# pa_only_900.net
KiCad netlist of a schematic drawn in EAGLE
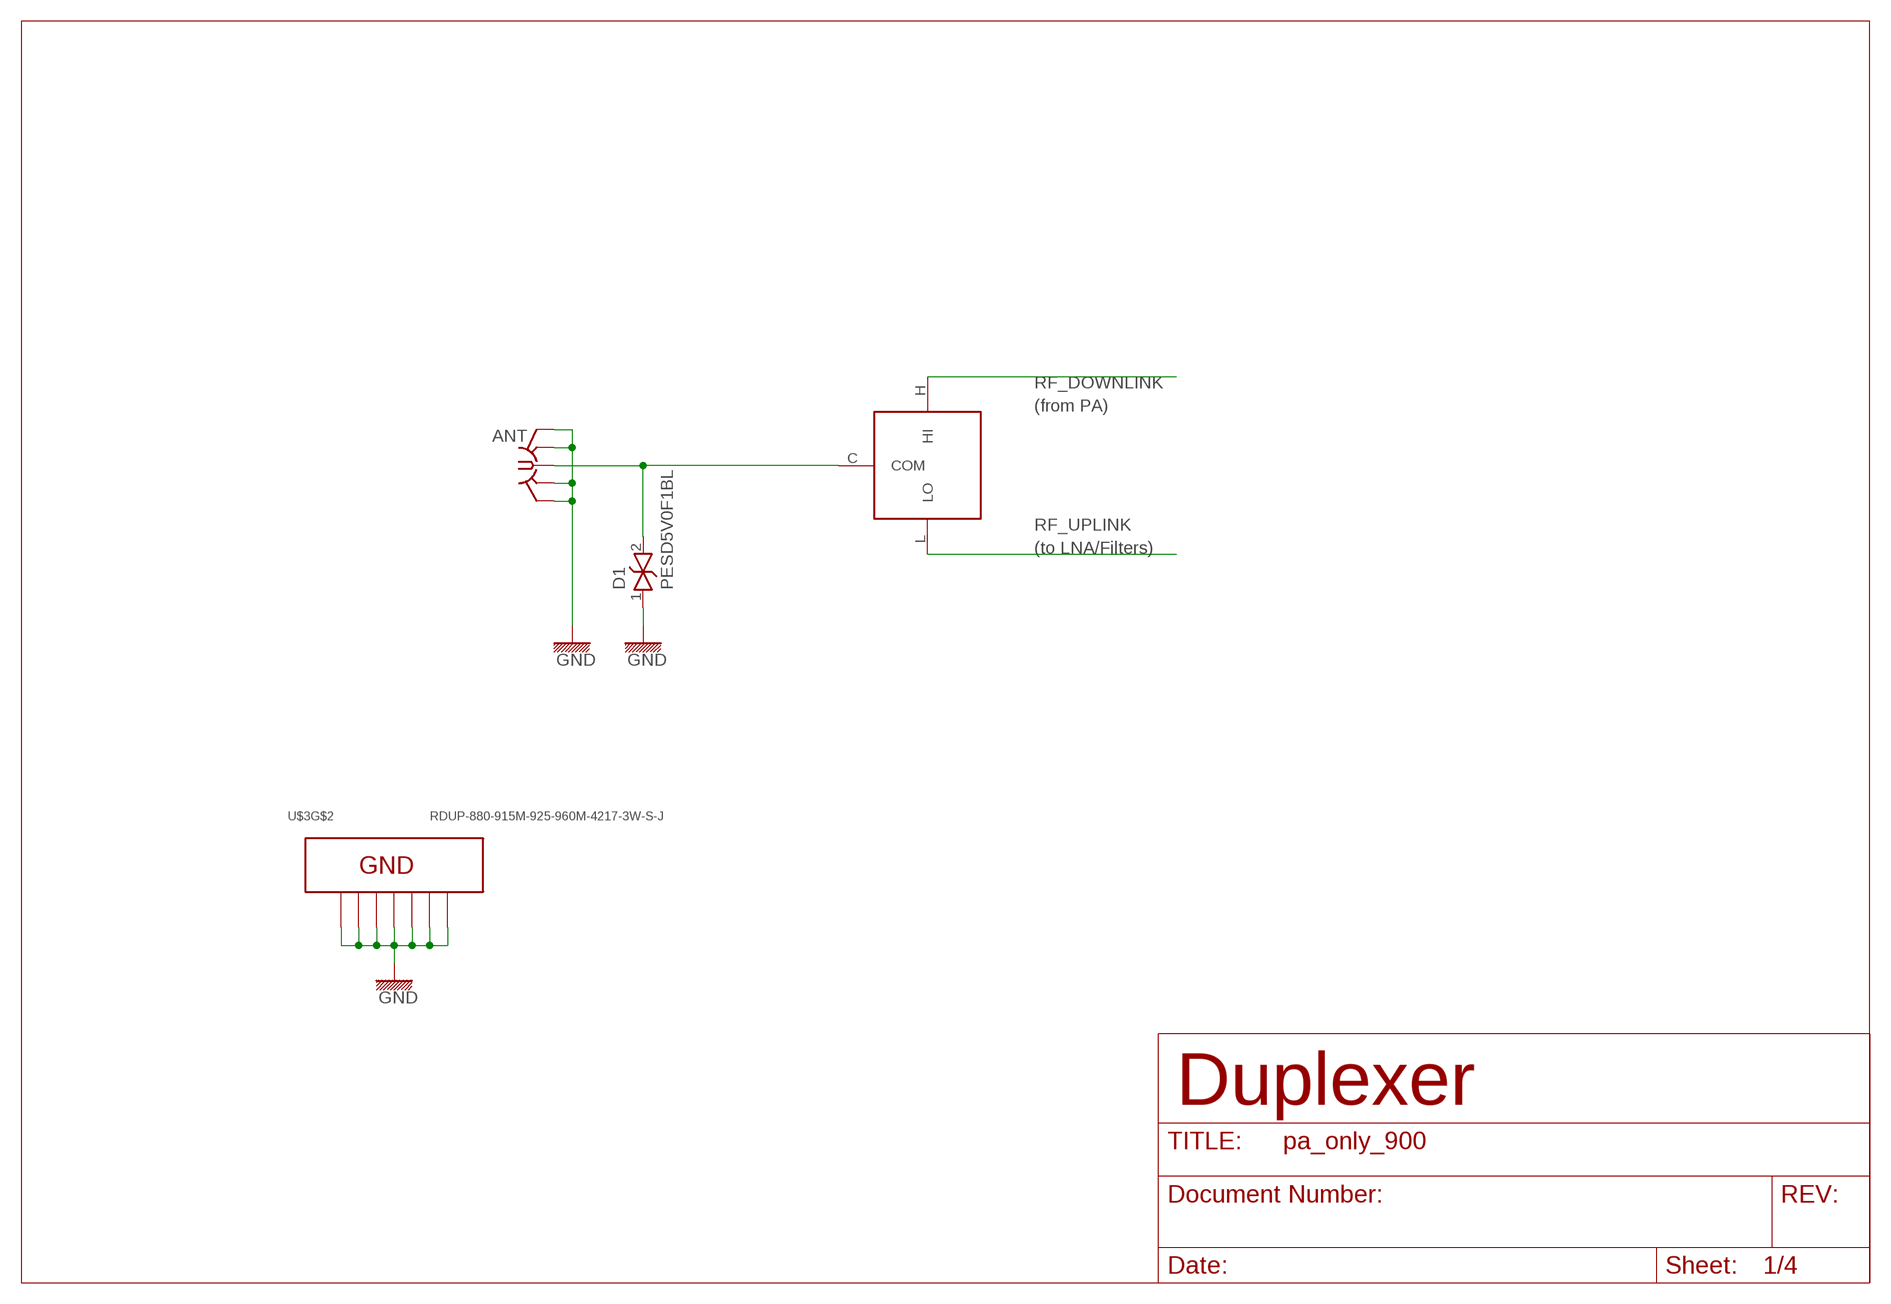
[diagram p0: schematic, sheet 1]
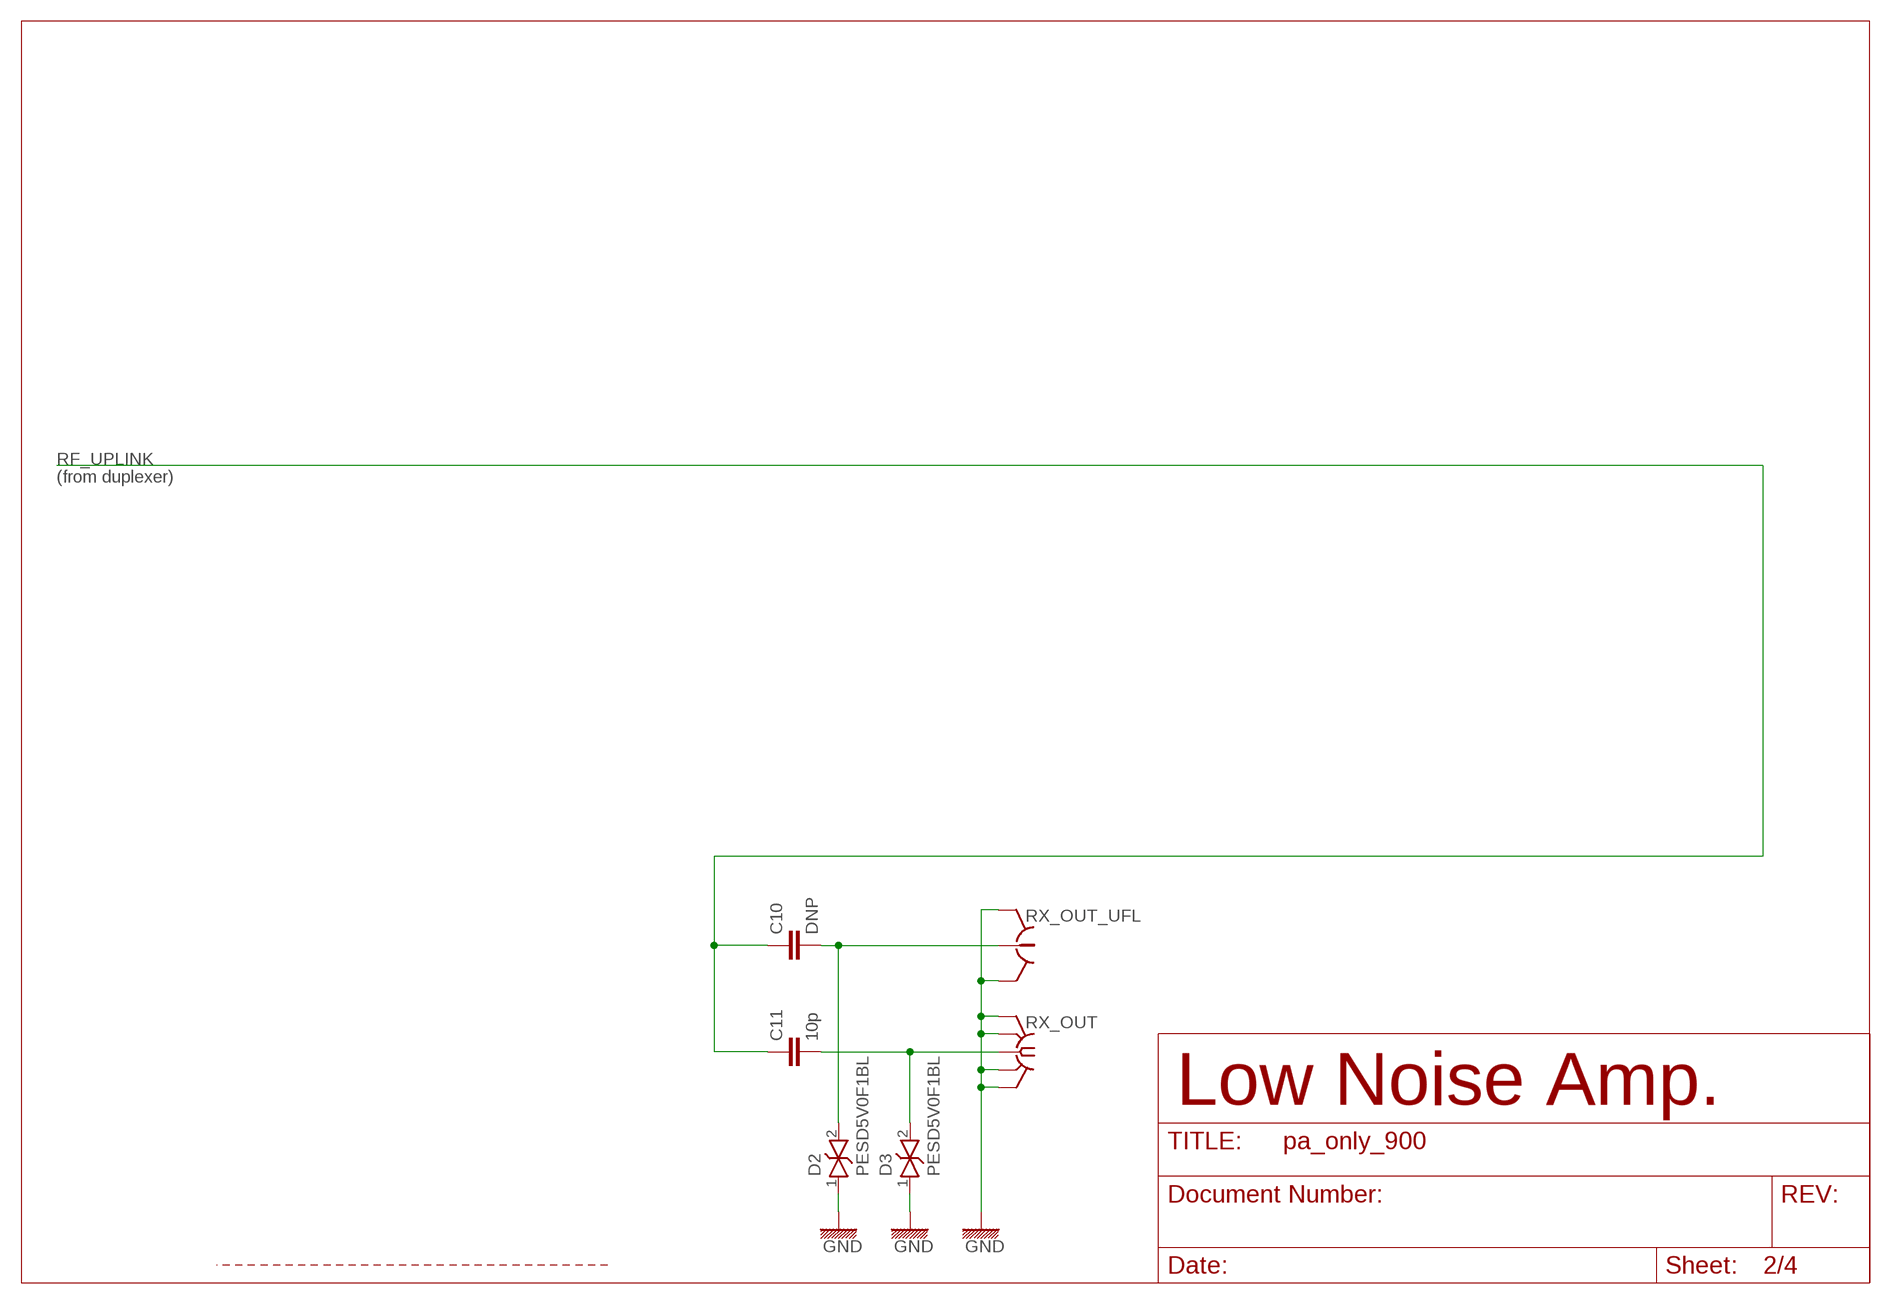
[diagram p1: schematic, sheet 2]
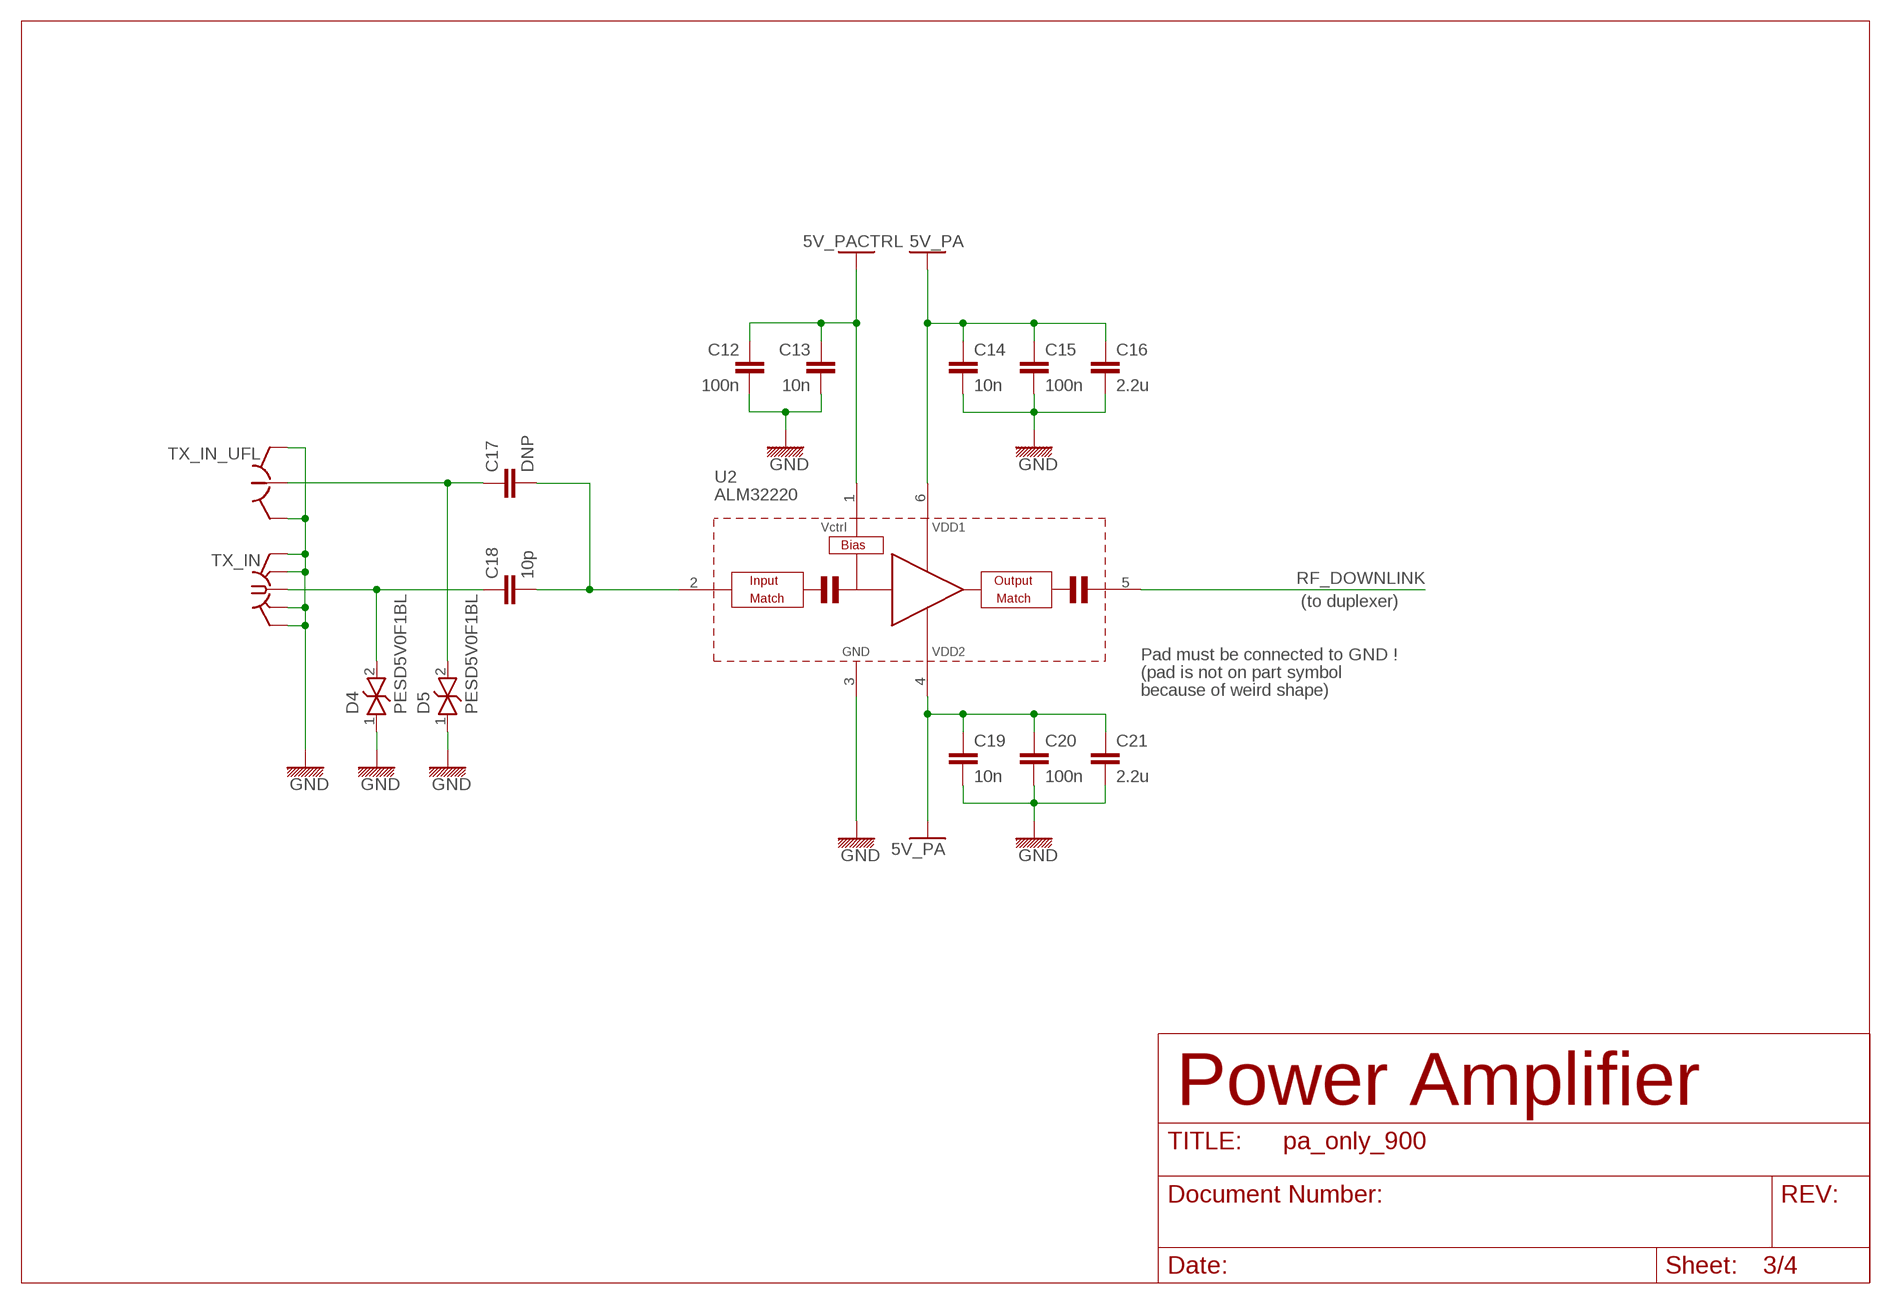
[diagram p2: schematic, sheet 3]
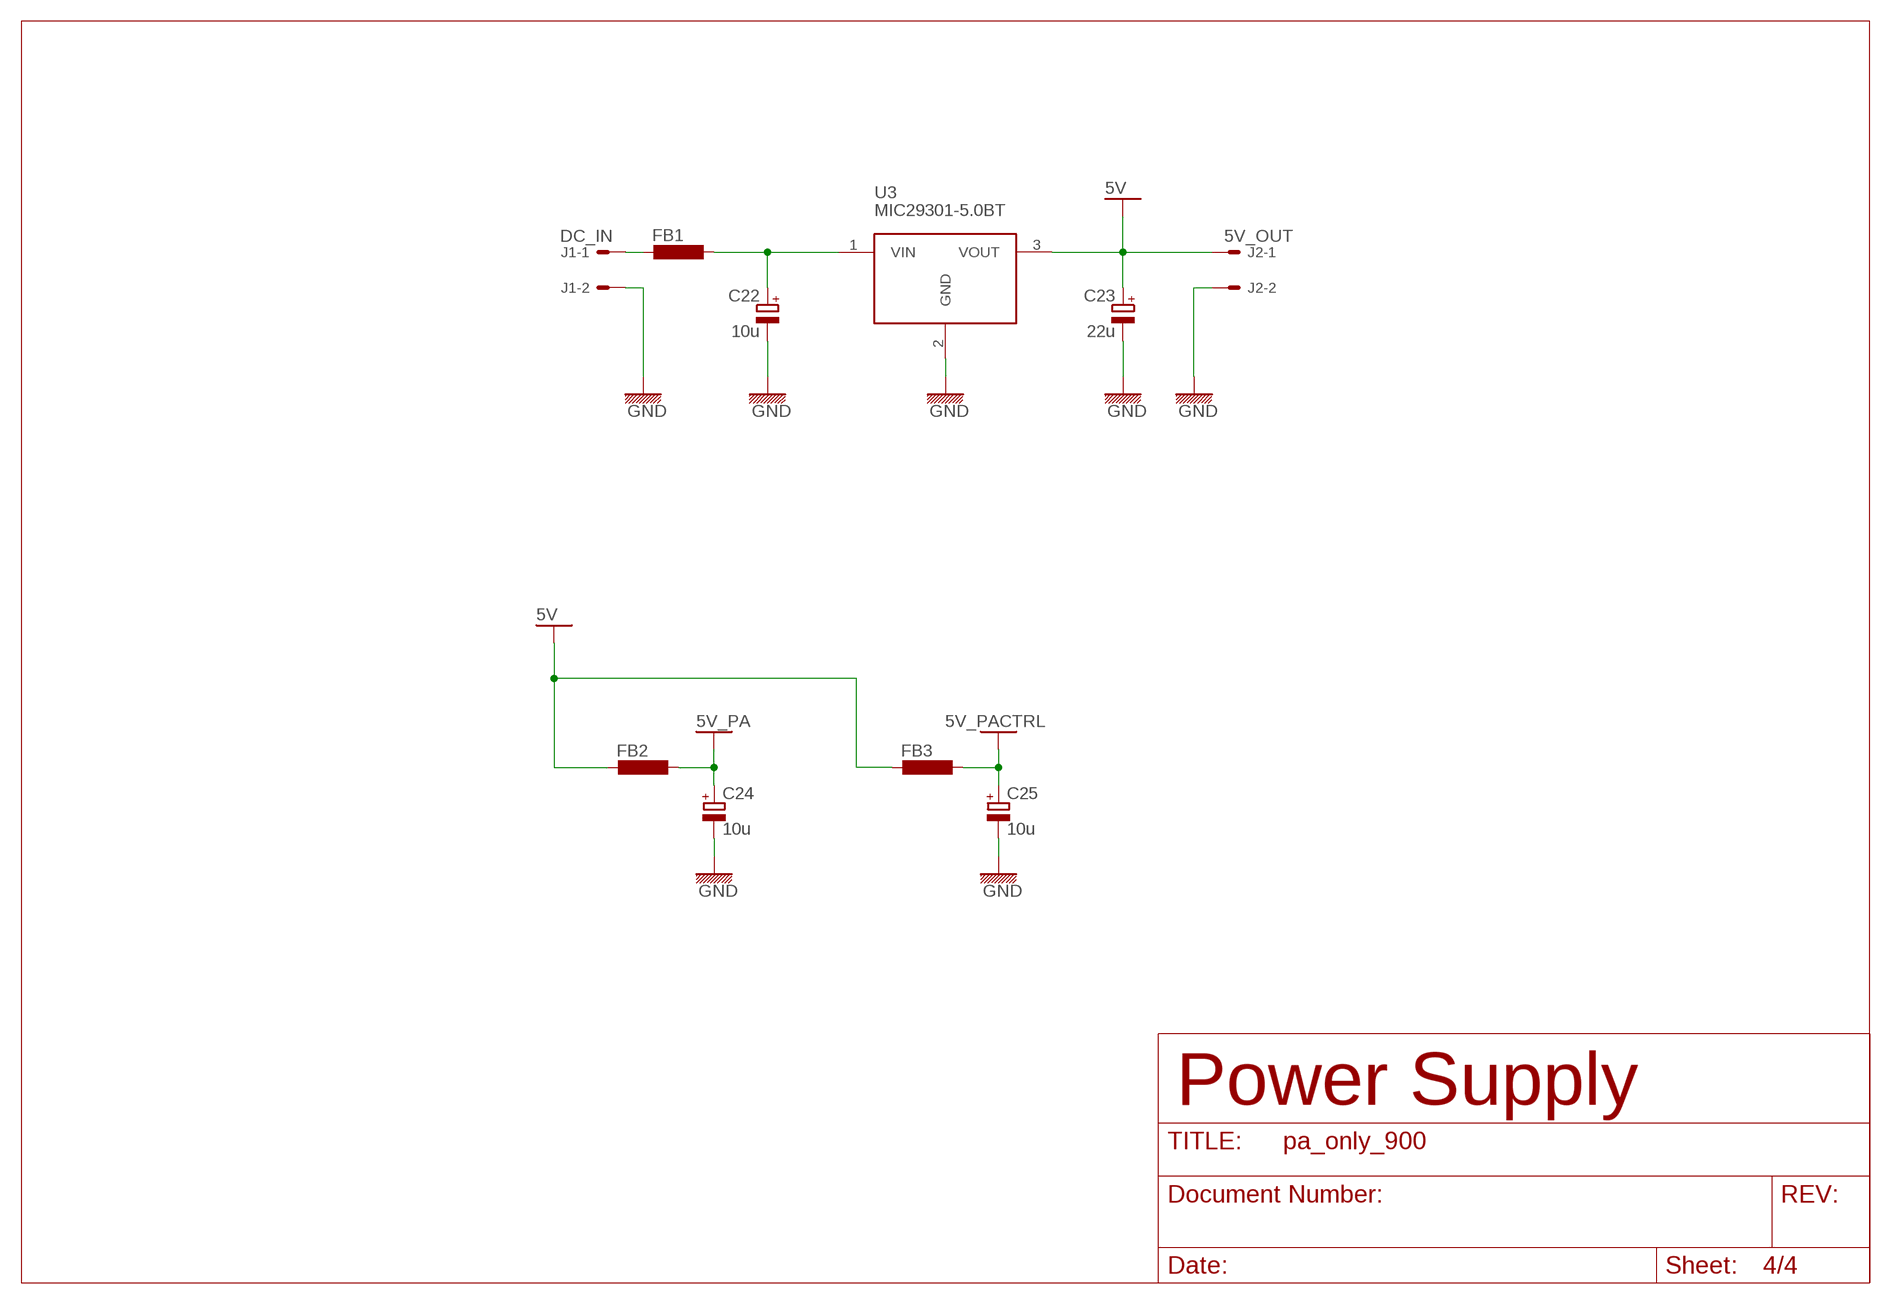
[diagram p3: schematic, sheet 4]

(export (version "E")
  (design (tool "Eeschema 10.0.6"))
  (components
    (comp (ref "ANT")
      (value "SMA-F-S-TH")
      (footprint "eagle-import:SMA-F-S-TH")
      (libsource (lib "eagle-import") (part "SMA-F-S-TH"))
    )
    (comp (ref "D1")
      (value "PESD5V0F1BL")
      (footprint "eagle-import:SOD882")
      (libsource (lib "eagle-import") (part "D_ESD_SOD882"))
    )
    (comp (ref "U$3")
      (value "RDUP-880-915M-925-960M-4217-3W-S-J")
      (footprint "eagle-import:RADITEK_4217")
      (libsource (lib "eagle-import") (part "RDUP-880-915M-925-960M-4217-3W-S-J"))
    )
    (comp (ref "C10")
      (value "DNP")
      (footprint "eagle-import:0603")
      (libsource (lib "eagle-import") (part "C-EU_0603"))
    )
    (comp (ref "C11")
      (value "10p")
      (footprint "eagle-import:0603")
      (libsource (lib "eagle-import") (part "C-EU_0603"))
    )
    (comp (ref "D2")
      (value "PESD5V0F1BL")
      (footprint "eagle-import:SOD882")
      (libsource (lib "eagle-import") (part "D_ESD_SOD882"))
    )
    (comp (ref "D3")
      (value "PESD5V0F1BL")
      (footprint "eagle-import:SOD882")
      (libsource (lib "eagle-import") (part "D_ESD_SOD882"))
    )
    (comp (ref "RX_OUT")
      (value "SMA-F-S-TH")
      (footprint "eagle-import:SMA-F-S-TH")
      (libsource (lib "eagle-import") (part "SMA-F-S-TH"))
    )
    (comp (ref "RX_OUT_UFL")
      (value "HRS_UFL")
      (footprint "eagle-import:HRS_UFL")
      (libsource (lib "eagle-import") (part "HRS_UFL"))
    )
    (comp (ref "C12")
      (value "100n")
      (footprint "eagle-import:0603")
      (libsource (lib "eagle-import") (part "C-EU_0603"))
    )
    (comp (ref "C13")
      (value "10n")
      (footprint "eagle-import:0603")
      (libsource (lib "eagle-import") (part "C-EU_0603"))
    )
    (comp (ref "C14")
      (value "10n")
      (footprint "eagle-import:0603")
      (libsource (lib "eagle-import") (part "C-EU_0603"))
    )
    (comp (ref "C15")
      (value "100n")
      (footprint "eagle-import:0603")
      (libsource (lib "eagle-import") (part "C-EU_0603"))
    )
    (comp (ref "C16")
      (value "2.2u")
      (footprint "eagle-import:0805")
      (libsource (lib "eagle-import") (part "C-EU_0805"))
    )
    (comp (ref "C17")
      (value "DNP")
      (footprint "eagle-import:0603")
      (libsource (lib "eagle-import") (part "C-EU_0603"))
    )
    (comp (ref "C18")
      (value "10p")
      (footprint "eagle-import:0603")
      (libsource (lib "eagle-import") (part "C-EU_0603"))
    )
    (comp (ref "C19")
      (value "10n")
      (footprint "eagle-import:0603")
      (libsource (lib "eagle-import") (part "C-EU_0603"))
    )
    (comp (ref "C20")
      (value "100n")
      (footprint "eagle-import:0603")
      (libsource (lib "eagle-import") (part "C-EU_0603"))
    )
    (comp (ref "C21")
      (value "2.2u")
      (footprint "eagle-import:0805")
      (libsource (lib "eagle-import") (part "C-EU_0805"))
    )
    (comp (ref "D4")
      (value "PESD5V0F1BL")
      (footprint "eagle-import:SOD882")
      (libsource (lib "eagle-import") (part "D_ESD_SOD882"))
    )
    (comp (ref "D5")
      (value "PESD5V0F1BL")
      (footprint "eagle-import:SOD882")
      (libsource (lib "eagle-import") (part "D_ESD_SOD882"))
    )
    (comp (ref "TX_IN")
      (value "SMA-F-S-TH")
      (footprint "eagle-import:SMA-F-S-TH")
      (libsource (lib "eagle-import") (part "SMA-F-S-TH"))
    )
    (comp (ref "TX_IN_UFL")
      (value "HRS_UFL")
      (footprint "eagle-import:HRS_UFL")
      (libsource (lib "eagle-import") (part "HRS_UFL"))
    )
    (comp (ref "U2")
      (value "ALM32220")
      (footprint "eagle-import:ALM32X20")
      (libsource (lib "eagle-import") (part "ALM32220"))
    )
    (comp (ref "C22")
      (value "10u")
      (footprint "eagle-import:SMC_A")
      (libsource (lib "eagle-import") (part "CPOL-EUSMCA"))
    )
    (comp (ref "C23")
      (value "22u")
      (footprint "eagle-import:SMC_A")
      (libsource (lib "eagle-import") (part "CPOL-EUSMCA"))
    )
    (comp (ref "C24")
      (value "10u")
      (footprint "eagle-import:SMC_A")
      (libsource (lib "eagle-import") (part "CPOL-EUSMCA"))
    )
    (comp (ref "C25")
      (value "10u")
      (footprint "eagle-import:SMC_A")
      (libsource (lib "eagle-import") (part "CPOL-EUSMCA"))
    )
    (comp (ref "FB1")
      (value "FBEAD_1206")
      (footprint "eagle-import:1206")
      (libsource (lib "eagle-import") (part "FBEAD_1206"))
    )
    (comp (ref "FB2")
      (value "FBEAD_1206")
      (footprint "eagle-import:1206")
      (libsource (lib "eagle-import") (part "FBEAD_1206"))
    )
    (comp (ref "FB3")
      (value "FBEAD_0603")
      (footprint "eagle-import:0603")
      (libsource (lib "eagle-import") (part "FBEAD_0603"))
    )
    (comp (ref "J1")
      (value "DC_IN")
      (footprint "eagle-import:6410-02")
      (libsource (lib "eagle-import") (part "22-?-0227-2021"))
    )
    (comp (ref "J2")
      (value "5V_OUT")
      (footprint "eagle-import:6410-02")
      (fields (field (name "OC_FARNELL") "unknown") (field (name "OC_NEWARK") "unknown"))
      (libsource (lib "eagle-import") (part "22-?-0227-2021"))
    )
    (comp (ref "U3")
      (value "MIC29301-5.0BT")
      (footprint "eagle-import:TO220BV")
      (libsource (lib "eagle-import") (part "MIC29XXX-FIX_WT_TO220BV"))
    )
  )
  (nets
    (net (code "1") (name "5V") (class "Default")
      (node (ref "C23") (pin "+") (pinfunction "+_+") (pintype "passive"))
      (node (ref "FB2") (pin "1") (pinfunction "1_1") (pintype "passive"))
      (node (ref "FB3") (pin "1") (pinfunction "1_1") (pintype "passive"))
      (node (ref "J2") (pin "1") (pinfunction "S_1") (pintype "passive"))
      (node (ref "U3") (pin "3") (pinfunction "VOUT_3") (pintype "power_in"))
    )
    (net (code "2") (name "5V_PA") (class "Default")
      (node (ref "C14") (pin "1") (pinfunction "1_1") (pintype "passive"))
      (node (ref "C15") (pin "1") (pinfunction "1_1") (pintype "passive"))
      (node (ref "C16") (pin "1") (pinfunction "1_1") (pintype "passive"))
      (node (ref "C19") (pin "1") (pinfunction "1_1") (pintype "passive"))
      (node (ref "C20") (pin "1") (pinfunction "1_1") (pintype "passive"))
      (node (ref "C21") (pin "1") (pinfunction "1_1") (pintype "passive"))
      (node (ref "C24") (pin "+") (pinfunction "+_+") (pintype "passive"))
      (node (ref "FB2") (pin "2") (pinfunction "2_2") (pintype "passive"))
      (node (ref "U2") (pin "4") (pinfunction "VDD2_4") (pintype "power_in"))
      (node (ref "U2") (pin "6") (pinfunction "VDD1_6") (pintype "power_in"))
    )
    (net (code "3") (name "5V_PACTRL") (class "Default")
      (node (ref "C12") (pin "1") (pinfunction "1_1") (pintype "passive"))
      (node (ref "C13") (pin "1") (pinfunction "1_1") (pintype "passive"))
      (node (ref "C25") (pin "+") (pinfunction "+_+") (pintype "passive"))
      (node (ref "FB3") (pin "2") (pinfunction "2_2") (pintype "passive"))
      (node (ref "U2") (pin "1") (pinfunction "VCTRL_1") (pintype "power_in"))
    )
    (net (code "4") (name "GND") (class "Default")
      (node (ref "ANT") (pin "G1") (pinfunction "GND_G1") (pintype "power_in"))
      (node (ref "ANT") (pin "G2") (pinfunction "GND_G2") (pintype "power_in"))
      (node (ref "ANT") (pin "G3") (pinfunction "GND_G3") (pintype "power_in"))
      (node (ref "ANT") (pin "G4") (pinfunction "GND_G4") (pintype "power_in"))
      (node (ref "C12") (pin "2") (pinfunction "2_2") (pintype "passive"))
      (node (ref "C13") (pin "2") (pinfunction "2_2") (pintype "passive"))
      (node (ref "C14") (pin "2") (pinfunction "2_2") (pintype "passive"))
      (node (ref "C15") (pin "2") (pinfunction "2_2") (pintype "passive"))
      (node (ref "C16") (pin "2") (pinfunction "2_2") (pintype "passive"))
      (node (ref "C19") (pin "2") (pinfunction "2_2") (pintype "passive"))
      (node (ref "C20") (pin "2") (pinfunction "2_2") (pintype "passive"))
      (node (ref "C21") (pin "2") (pinfunction "2_2") (pintype "passive"))
      (node (ref "C22") (pin "-") (pinfunction "-_-") (pintype "passive"))
      (node (ref "C23") (pin "-") (pinfunction "-_-") (pintype "passive"))
      (node (ref "C24") (pin "-") (pinfunction "-_-") (pintype "passive"))
      (node (ref "C25") (pin "-") (pinfunction "-_-") (pintype "passive"))
      (node (ref "D1") (pin "1") (pinfunction "1_1") (pintype "passive"))
      (node (ref "D2") (pin "1") (pinfunction "1_1") (pintype "passive"))
      (node (ref "D3") (pin "1") (pinfunction "1_1") (pintype "passive"))
      (node (ref "D4") (pin "1") (pinfunction "1_1") (pintype "passive"))
      (node (ref "D5") (pin "1") (pinfunction "1_1") (pintype "passive"))
      (node (ref "J1") (pin "2") (pinfunction "S_2") (pintype "passive"))
      (node (ref "J2") (pin "2") (pinfunction "S_2") (pintype "passive"))
      (node (ref "RX_OUT") (pin "G1") (pinfunction "GND_G1") (pintype "power_in"))
      (node (ref "RX_OUT") (pin "G2") (pinfunction "GND_G2") (pintype "power_in"))
      (node (ref "RX_OUT") (pin "G3") (pinfunction "GND_G3") (pintype "power_in"))
      (node (ref "RX_OUT") (pin "G4") (pinfunction "GND_G4") (pintype "power_in"))
      (node (ref "RX_OUT_UFL") (pin "GND@1") (pinfunction "GND_GND@1") (pintype "power_in"))
      (node (ref "RX_OUT_UFL") (pin "GND@2") (pinfunction "GND_GND@2") (pintype "power_in"))
      (node (ref "TX_IN") (pin "G1") (pinfunction "GND_G1") (pintype "power_in"))
      (node (ref "TX_IN") (pin "G2") (pinfunction "GND_G2") (pintype "power_in"))
      (node (ref "TX_IN") (pin "G3") (pinfunction "GND_G3") (pintype "power_in"))
      (node (ref "TX_IN") (pin "G4") (pinfunction "GND_G4") (pintype "power_in"))
      (node (ref "TX_IN_UFL") (pin "GND@1") (pinfunction "GND_GND@1") (pintype "power_in"))
      (node (ref "TX_IN_UFL") (pin "GND@2") (pinfunction "GND_GND@2") (pintype "power_in"))
      (node (ref "U$3") (pin "G1") (pinfunction "P$1_G1") (pintype "bidirectional"))
      (node (ref "U$3") (pin "G2") (pinfunction "P$2_G2") (pintype "bidirectional"))
      (node (ref "U$3") (pin "G3") (pinfunction "P$3_G3") (pintype "bidirectional"))
      (node (ref "U$3") (pin "G4") (pinfunction "P$4_G4") (pintype "bidirectional"))
      (node (ref "U$3") (pin "G5") (pinfunction "P$5_G5") (pintype "bidirectional"))
      (node (ref "U$3") (pin "G6") (pinfunction "P$6_G6") (pintype "bidirectional"))
      (node (ref "U$3") (pin "G7") (pinfunction "P$7_G7") (pintype "bidirectional"))
      (node (ref "U2") (pin "3") (pinfunction "GND_3") (pintype "power_in"))
      (node (ref "U3") (pin "2") (pinfunction "GND_2") (pintype "power_in"))
    )
    (net (code "5") (name "Net-(ANT-1)") (class "Default")
      (node (ref "ANT") (pin "C") (pinfunction "1_C") (pintype "passive"))
      (node (ref "D1") (pin "2") (pinfunction "2_2") (pintype "passive"))
      (node (ref "U$3") (pin "C") (pinfunction "COM_C") (pintype "bidirectional"))
    )
    (net (code "6") (name "Net-(J1A-S)") (class "Default")
      (node (ref "FB1") (pin "1") (pinfunction "1_1") (pintype "passive"))
      (node (ref "J1") (pin "1") (pinfunction "S_1") (pintype "passive"))
    )
    (net (code "7") (name "Net-(RX_OUT-1)") (class "Default")
      (node (ref "C11") (pin "2") (pinfunction "2_2") (pintype "passive"))
      (node (ref "D3") (pin "2") (pinfunction "2_2") (pintype "passive"))
      (node (ref "RX_OUT") (pin "C") (pinfunction "1_C") (pintype "passive"))
    )
    (net (code "8") (name "Net-(RX_OUT_UFL-1)") (class "Default")
      (node (ref "C10") (pin "2") (pinfunction "2_2") (pintype "passive"))
      (node (ref "D2") (pin "2") (pinfunction "2_2") (pintype "passive"))
      (node (ref "RX_OUT_UFL") (pin "SIG") (pinfunction "1_SIG") (pintype "passive"))
    )
    (net (code "9") (name "Net-(TX_IN-1)") (class "Default")
      (node (ref "C18") (pin "1") (pinfunction "1_1") (pintype "passive"))
      (node (ref "D4") (pin "2") (pinfunction "2_2") (pintype "passive"))
      (node (ref "TX_IN") (pin "C") (pinfunction "1_C") (pintype "passive"))
    )
    (net (code "10") (name "Net-(TX_IN_UFL-1)") (class "Default")
      (node (ref "C17") (pin "1") (pinfunction "1_1") (pintype "passive"))
      (node (ref "D5") (pin "2") (pinfunction "2_2") (pintype "passive"))
      (node (ref "TX_IN_UFL") (pin "SIG") (pinfunction "1_SIG") (pintype "passive"))
    )
    (net (code "11") (name "Net-(U2-RF_IN)") (class "Default")
      (node (ref "C17") (pin "2") (pinfunction "2_2") (pintype "passive"))
      (node (ref "C18") (pin "2") (pinfunction "2_2") (pintype "passive"))
      (node (ref "U2") (pin "2") (pinfunction "RF_IN_2") (pintype "input"))
    )
    (net (code "12") (name "Net-(U3-VIN)") (class "Default")
      (node (ref "C22") (pin "+") (pinfunction "+_+") (pintype "passive"))
      (node (ref "FB1") (pin "2") (pinfunction "2_2") (pintype "passive"))
      (node (ref "U3") (pin "1") (pinfunction "VIN_1") (pintype "power_in"))
    )
    (net (code "13") (name "RF_DOWNLINK") (class "Default")
      (node (ref "U$3") (pin "H") (pinfunction "HI_H") (pintype "bidirectional"))
      (node (ref "U2") (pin "5") (pinfunction "RF_OUT_5") (pintype "output"))
    )
    (net (code "14") (name "RF_UPLINK") (class "Default")
      (node (ref "C10") (pin "1") (pinfunction "1_1") (pintype "passive"))
      (node (ref "C11") (pin "1") (pinfunction "1_1") (pintype "passive"))
      (node (ref "U$3") (pin "L") (pinfunction "LO_L") (pintype "bidirectional"))
    )
  )
)
